# IO_ports.net
KiCad netlist of a schematic drawn in EAGLE
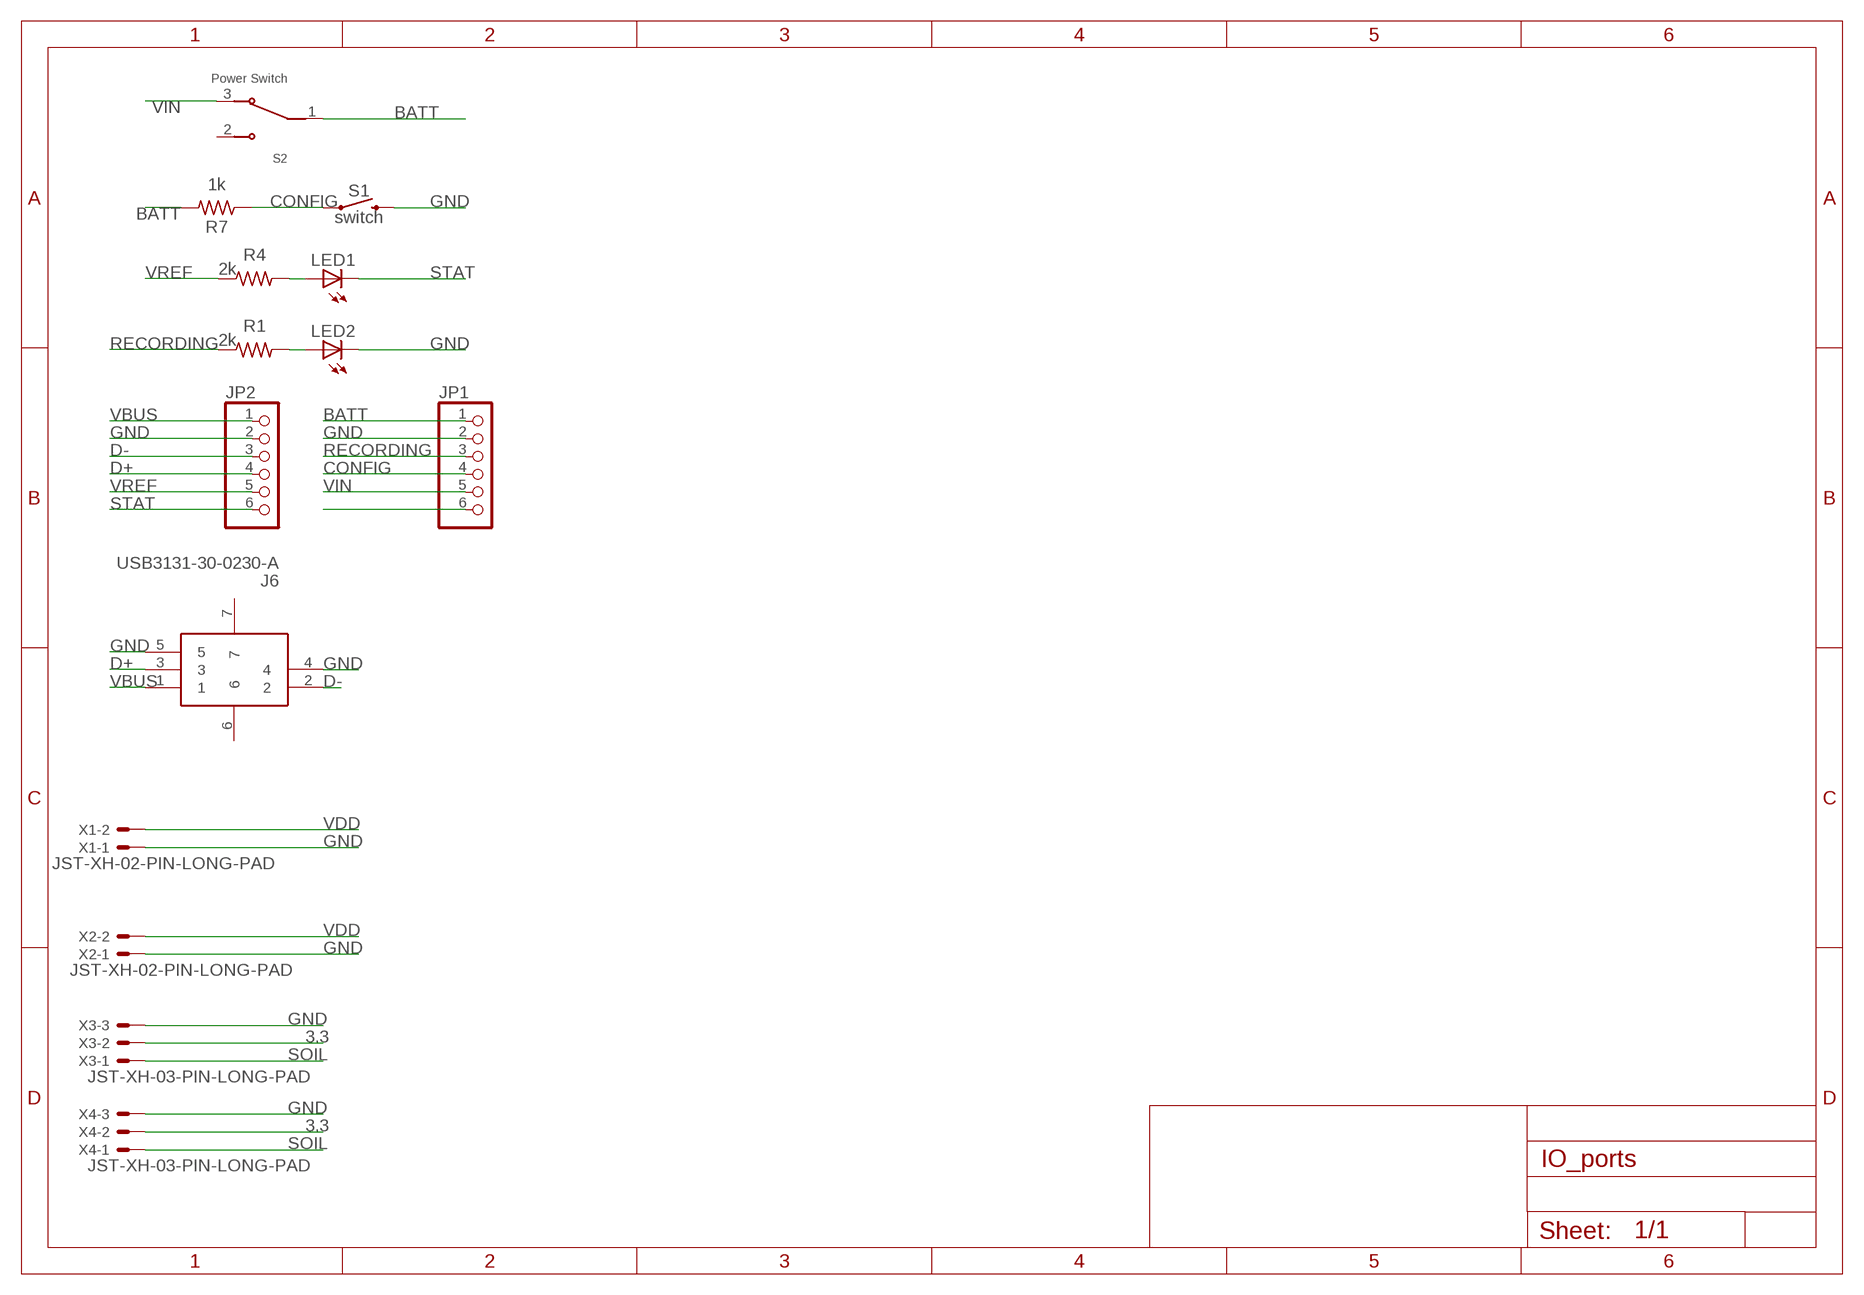
[diagram p0: schematic, sheet 1]

(export (version "E")
  (design (tool "Eeschema 10.0.6"))
  (components
    (comp (ref "J6")
      (value "USB3131-30-0230-A")
      (footprint "eagle-import:USB3131300230A")
      (fields (field (name "MOUSER_PART_NUMBER") "640-USB3131300230A"))
      (libsource (lib "eagle-import") (part "USB3131-30-0230-A"))
    )
    (comp (ref "JP1")
      (value "PINHD-1X6JSTXH")
      (footprint "eagle-import:JST-XH-06-PACKAGE-ROUND-PAD")
      (libsource (lib "eagle-import") (part "PINHD-1X6JSTXH"))
    )
    (comp (ref "JP2")
      (value "PINHD-1X6JSTXH")
      (footprint "eagle-import:JST-XH-06-PACKAGE-ROUND-PAD")
      (libsource (lib "eagle-import") (part "PINHD-1X6JSTXH"))
    )
    (comp (ref "LED1")
      (value "LEDCHIP-LED0805")
      (footprint "eagle-import:CHIP-LED0805")
      (libsource (lib "eagle-import") (part "LEDCHIP-LED0805"))
    )
    (comp (ref "LED2")
      (value "LEDCHIP-LED0805")
      (footprint "eagle-import:CHIP-LED0805")
      (libsource (lib "eagle-import") (part "LEDCHIP-LED0805"))
    )
    (comp (ref "R1")
      (value "2k")
      (footprint "eagle-import:M0805")
      (libsource (lib "eagle-import") (part "R-US_M0805"))
    )
    (comp (ref "R4")
      (value "2k")
      (footprint "eagle-import:M0805")
      (libsource (lib "eagle-import") (part "R-US_M0805"))
    )
    (comp (ref "R7")
      (value "1k")
      (footprint "eagle-import:RESC2012X65")
      (libsource (lib "eagle-import") (part "R-USCHIP-0805(2012-METRIC)_"))
    )
    (comp (ref "S1")
      (value "switch")
      (footprint "eagle-import:TACTILE_SWITCH_PTH_6.0MM")
      (libsource (lib "eagle-import") (part "MOMENTARY-SWITCH-SPST-PTH-6.0MM"))
    )
    (comp (ref "S2")
      (value "Power Switch")
      (footprint "eagle-import:SW_MSS-102545-28A-D")
      (fields (field (name "MF") "CUI Devices") (field (name "MP") "MSS-102545-28A-D"))
      (libsource (lib "eagle-import") (part "MSS-102545-28A-D"))
    )
    (comp (ref "X1")
      (value "JST-XH-02-PIN-LONG-PAD")
      (footprint "eagle-import:JST-XH-02-PACKAGE-LONG-PAD")
      (libsource (lib "eagle-import") (part "JST-XH-02-PIN-LONG-PAD"))
    )
    (comp (ref "X2")
      (value "JST-XH-02-PIN-LONG-PAD")
      (footprint "eagle-import:JST-XH-02-PACKAGE-LONG-PAD")
      (libsource (lib "eagle-import") (part "JST-XH-02-PIN-LONG-PAD"))
    )
    (comp (ref "X3")
      (value "JST-XH-03-PIN-LONG-PAD")
      (footprint "eagle-import:JST-XH-03-PACKAGE-LONG-PAD")
      (libsource (lib "eagle-import") (part "JST-XH-03-PIN-LONG-PAD"))
    )
    (comp (ref "X4")
      (value "JST-XH-03-PIN-LONG-PAD")
      (footprint "eagle-import:JST-XH-03-PACKAGE-LONG-PAD")
      (libsource (lib "eagle-import") (part "JST-XH-03-PIN-LONG-PAD"))
    )
  )
  (nets
    (net (code "1") (name "/3.3") (class "Default")
      (node (ref "X3") (pin "2") (pinfunction "S_2") (pintype "passive"))
      (node (ref "X4") (pin "2") (pinfunction "S_2") (pintype "passive"))
    )
    (net (code "2") (name "/BATT") (class "Default")
      (node (ref "JP1") (pin "1") (pinfunction "1_1") (pintype "passive"))
      (node (ref "R7") (pin "2") (pinfunction "2_2") (pintype "passive"))
      (node (ref "S2") (pin "1") (pinfunction "1_1") (pintype "passive"))
    )
    (net (code "3") (name "/CONFIG") (class "Default")
      (node (ref "JP1") (pin "4") (pinfunction "4_4") (pintype "passive"))
      (node (ref "R7") (pin "1") (pinfunction "1_1") (pintype "passive"))
      (node (ref "S1") (pin "1") (pinfunction "1_1") (pintype "passive"))
    )
    (net (code "4") (name "/D+") (class "Default")
      (node (ref "J6") (pin "3") (pinfunction "3_3") (pintype "bidirectional"))
      (node (ref "JP2") (pin "4") (pinfunction "4_4") (pintype "passive"))
    )
    (net (code "5") (name "/D-") (class "Default")
      (node (ref "J6") (pin "2") (pinfunction "2_2") (pintype "bidirectional"))
      (node (ref "JP2") (pin "3") (pinfunction "3_3") (pintype "passive"))
    )
    (net (code "6") (name "/GND") (class "Default")
      (node (ref "J6") (pin "4") (pinfunction "4_4") (pintype "bidirectional"))
      (node (ref "J6") (pin "5") (pinfunction "5_5") (pintype "bidirectional"))
      (node (ref "JP1") (pin "2") (pinfunction "2_2") (pintype "passive"))
      (node (ref "JP2") (pin "2") (pinfunction "2_2") (pintype "passive"))
      (node (ref "LED2") (pin "C") (pinfunction "C_C") (pintype "passive"))
      (node (ref "S1") (pin "3") (pinfunction "2_3") (pintype "passive"))
      (node (ref "X1") (pin "1") (pinfunction "S_1") (pintype "passive"))
      (node (ref "X2") (pin "1") (pinfunction "S_1") (pintype "passive"))
      (node (ref "X3") (pin "3") (pinfunction "S_3") (pintype "passive"))
      (node (ref "X4") (pin "3") (pinfunction "S_3") (pintype "passive"))
    )
    (net (code "7") (name "/RECORDING") (class "Default")
      (node (ref "JP1") (pin "3") (pinfunction "3_3") (pintype "passive"))
      (node (ref "R1") (pin "1") (pinfunction "1_1") (pintype "passive"))
    )
    (net (code "8") (name "/SOIL") (class "Default")
      (node (ref "X3") (pin "1") (pinfunction "S_1") (pintype "passive"))
      (node (ref "X4") (pin "1") (pinfunction "S_1") (pintype "passive"))
    )
    (net (code "9") (name "/STAT") (class "Default")
      (node (ref "JP2") (pin "6") (pinfunction "6_6") (pintype "passive"))
      (node (ref "LED1") (pin "C") (pinfunction "C_C") (pintype "passive"))
    )
    (net (code "10") (name "/VBUS") (class "Default")
      (node (ref "J6") (pin "1") (pinfunction "1_1") (pintype "bidirectional"))
      (node (ref "JP2") (pin "1") (pinfunction "1_1") (pintype "passive"))
    )
    (net (code "11") (name "/VDD") (class "Default")
      (node (ref "X1") (pin "2") (pinfunction "S_2") (pintype "passive"))
      (node (ref "X2") (pin "2") (pinfunction "S_2") (pintype "passive"))
    )
    (net (code "12") (name "/VIN") (class "Default")
      (node (ref "JP1") (pin "5") (pinfunction "5_5") (pintype "passive"))
      (node (ref "S2") (pin "3") (pinfunction "3_3") (pintype "passive"))
    )
    (net (code "13") (name "/VREF") (class "Default")
      (node (ref "JP2") (pin "5") (pinfunction "5_5") (pintype "passive"))
      (node (ref "R4") (pin "1") (pinfunction "1_1") (pintype "passive"))
    )
    (net (code "14") (name "Net-(LED1-PadA)") (class "Default")
      (node (ref "LED1") (pin "A") (pinfunction "A_A") (pintype "passive"))
      (node (ref "R4") (pin "2") (pinfunction "2_2") (pintype "passive"))
    )
    (net (code "15") (name "Net-(LED2-PadA)") (class "Default")
      (node (ref "LED2") (pin "A") (pinfunction "A_A") (pintype "passive"))
      (node (ref "R1") (pin "2") (pinfunction "2_2") (pintype "passive"))
    )
    (net (code "16") (name "unconnected-(J6-Pad6)") (class "Default")
      (node (ref "J6") (pin "6") (pinfunction "6_6") (pintype "bidirectional"))
    )
    (net (code "17") (name "unconnected-(J6-Pad7)") (class "Default")
      (node (ref "J6") (pin "7") (pinfunction "7_7") (pintype "bidirectional"))
    )
    (net (code "18") (name "unconnected-(JP1-Pad6)") (class "Default")
      (node (ref "JP1") (pin "6") (pinfunction "6_6") (pintype "passive"))
    )
    (net (code "19") (name "unconnected-(S2-Pad2)") (class "Default")
      (node (ref "S2") (pin "2") (pinfunction "2_2") (pintype "passive"))
    )
  )
)
